# Optosense.net
KiCad netlist of a schematic drawn in Altium Designer
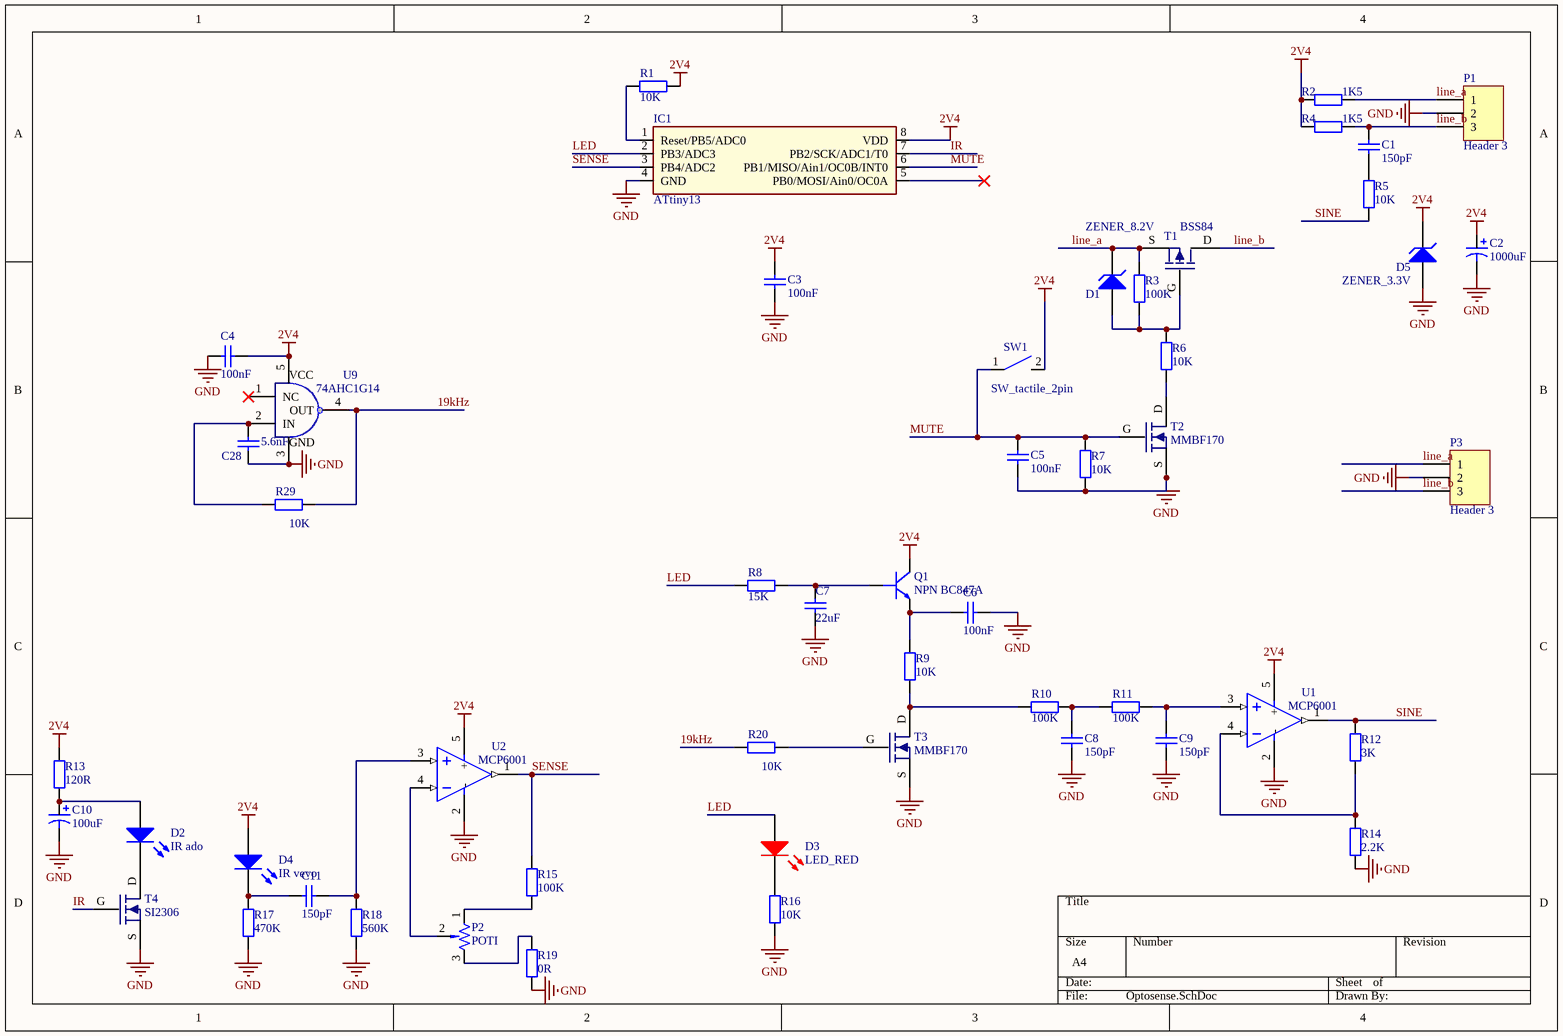
[diagram p0: Optosense.SchDoc]

(export (version "E")
  (design (tool "Eeschema 10.0.6"))
  (components
    (comp (ref "C1")
      (value "150pF")
      (footprint "FP_0603_CAP_080")
      (description "Capacitor")
      (libsource (lib "Capacitor") (part "CAP"))
    )
    (comp (ref "C2")
      (value "1000uF")
      (footprint "CAP_8x11_fekvo")
      (description "Polarized Capacitor")
      (libsource (lib "Capacitor") (part "CAP_ELECT"))
    )
    (comp (ref "C3")
      (value "100nF")
      (footprint "FP_0603_CAP_080")
      (description "Capacitor")
      (libsource (lib "Capacitor") (part "CAP"))
    )
    (comp (ref "C4")
      (value "100nF")
      (footprint "FP_0603_CAP_080")
      (description "Capacitor")
      (libsource (lib "Capacitor") (part "CAP"))
    )
    (comp (ref "C5")
      (value "100nF")
      (footprint "FP_0603_CAP_080")
      (description "Capacitor")
      (libsource (lib "Capacitor") (part "CAP"))
    )
    (comp (ref "C6")
      (value "100nF")
      (footprint "FP_0603_CAP_080")
      (description "Capacitor")
      (libsource (lib "Capacitor") (part "CAP"))
    )
    (comp (ref "C7")
      (value "22uF")
      (footprint "FP_1206_CAP_125")
      (description "Capacitor")
      (libsource (lib "Miscellaneous Devices") (part "Cap"))
    )
    (comp (ref "C8")
      (value "150pF")
      (footprint "FP_0603_CAP_080")
      (description "Capacitor")
      (libsource (lib "Capacitor") (part "CAP"))
    )
    (comp (ref "C9")
      (value "150pF")
      (footprint "FP_0603_CAP_080")
      (description "Capacitor")
      (libsource (lib "Capacitor") (part "CAP"))
    )
    (comp (ref "C10")
      (value "100uF")
      (footprint "FP_3528")
      (description "Polarized Capacitor")
      (libsource (lib "Capacitor") (part "CAP_ELECT"))
    )
    (comp (ref "C11")
      (value "150pF")
      (footprint "FP_0603_CAP_080")
      (description "Capacitor")
      (libsource (lib "Capacitor") (part "CAP"))
    )
    (comp (ref "C28")
      (value "5.6nF")
      (footprint "FP_0603_CAP_080")
      (description "Capacitor")
      (fields (field (name "PUBLISHER") "Altium Limited"))
      (libsource (lib "Miscellaneous Devices") (part "Cap"))
    )
    (comp (ref "D1")
      (value "ZENER_8.2V")
      (footprint "SOD-80")
      (description "Zener Diode")
      (libsource (lib "Diode") (part "ZENER"))
    )
    (comp (ref "D2")
      (value "IR ado")
      (footprint "LED_IR_5mm")
      (description "Typical LED")
      (libsource (lib "Led_optical") (part "LED_B"))
    )
    (comp (ref "D3")
      (value "LED_RED")
      (footprint "led_3mm_standing R")
      (description "Typical LED")
      (libsource (lib "Led_optical") (part "LED_R"))
    )
    (comp (ref "D4")
      (value "IR vevo")
      (footprint "LED_IR_5mm")
      (description "Typical LED")
      (libsource (lib "Led_optical") (part "LED_B"))
    )
    (comp (ref "D5")
      (value "ZENER_3.3V")
      (footprint "SOD-80")
      (description "Zener Diode")
      (libsource (lib "Diode") (part "ZENER"))
    )
    (comp (ref "IC1") (value "ATtiny13") (footprint "WSON_n_SOIC8") (libsource (lib "uC") (part "ATtiny13")))
    (comp (ref "P1")
      (value "Header 3")
      (footprint "HDR1X3")
      (description "Header, 3-Pin")
      (fields (field (name "PUBLISHER") "Altium Limited"))
      (libsource (lib "Miscellaneous Connectors") (part "Header 3"))
    )
    (comp (ref "P2")
      (value "POTI")
      (footprint "RES_trimmer_helipot_mini_90")
      (libsource (lib "Resistor") (part "POTI"))
    )
    (comp (ref "P3")
      (value "Header 3")
      (footprint "HDR1X3")
      (description "Header, 3-Pin")
      (fields (field (name "PUBLISHER") "Altium Limited"))
      (libsource (lib "Miscellaneous Connectors") (part "Header 3"))
    )
    (comp (ref "Q1") (value "NPN BC847A") (footprint "TR_SOT23") (libsource (lib "Transistor") (part "NPN")))
    (comp (ref "R1")
      (value "10K")
      (footprint "FP_0603_RES")
      (description "Resistor")
      (libsource (lib "") (part "RES_3"))
    )
    (comp (ref "R2")
      (value "1K5")
      (footprint "FP_0603_RES")
      (description "Resistor")
      (libsource (lib "") (part "RES_2"))
    )
    (comp (ref "R3")
      (value "100K")
      (footprint "FP_0603_RES")
      (description "Resistor")
      (libsource (lib "") (part "RES_1"))
    )
    (comp (ref "R4")
      (value "1K5")
      (footprint "FP_0603_RES")
      (description "Resistor")
      (libsource (lib "") (part "RES_2"))
    )
    (comp (ref "R5")
      (value "10K")
      (footprint "FP_0603_RES")
      (description "Resistor")
      (libsource (lib "Resistor") (part "RES"))
    )
    (comp (ref "R6")
      (value "10K")
      (footprint "FP_0603_RES")
      (description "Resistor")
      (libsource (lib "") (part "RES_1"))
    )
    (comp (ref "R7")
      (value "10K")
      (footprint "FP_0603_RES")
      (description "Resistor")
      (libsource (lib "") (part "RES_1"))
    )
    (comp (ref "R8")
      (value "15K")
      (footprint "FP_0603_RES")
      (description "Resistor")
      (libsource (lib "") (part "RES_3"))
    )
    (comp (ref "R9")
      (value "10K")
      (footprint "FP_0603_RES")
      (description "Resistor")
      (libsource (lib "") (part "RES_1"))
    )
    (comp (ref "R10")
      (value "100K")
      (footprint "FP_0603_RES")
      (description "Resistor")
      (libsource (lib "") (part "RES_3"))
    )
    (comp (ref "R11")
      (value "100K")
      (footprint "FP_0603_RES")
      (description "Resistor")
      (libsource (lib "") (part "RES_3"))
    )
    (comp (ref "R12")
      (value "3K")
      (footprint "FP_0603_RES")
      (description "Resistor")
      (libsource (lib "") (part "RES_1"))
    )
    (comp (ref "R13")
      (value "120R")
      (footprint "FP_0603_RES")
      (description "Resistor")
      (libsource (lib "Resistor") (part "RES"))
    )
    (comp (ref "R14")
      (value "2.2K")
      (footprint "FP_0603_RES")
      (description "Resistor")
      (libsource (lib "") (part "RES_1"))
    )
    (comp (ref "R15")
      (value "100K")
      (footprint "FP_0603_RES")
      (description "Resistor")
      (libsource (lib "Resistor") (part "RES"))
    )
    (comp (ref "R16")
      (value "10K")
      (footprint "FP_0603_RES")
      (description "Resistor")
      (libsource (lib "Resistor") (part "RES"))
    )
    (comp (ref "R17")
      (value "470K")
      (footprint "FP_0603_RES")
      (description "Resistor")
      (libsource (lib "Resistor") (part "RES"))
    )
    (comp (ref "R18")
      (value "560K")
      (footprint "FP_0603_RES")
      (description "Resistor")
      (libsource (lib "Resistor") (part "RES"))
    )
    (comp (ref "R19")
      (value "0R")
      (footprint "FP_0603_RES")
      (description "Resistor")
      (libsource (lib "Resistor") (part "RES"))
    )
    (comp (ref "R20")
      (value "10K")
      (footprint "FP_0603_RES")
      (description "Resistor")
      (fields (field (name "PUBLISHER") "Altium Limited"))
      (libsource (lib "Miscellaneous Devices") (part "Res3"))
    )
    (comp (ref "R29")
      (value "10K")
      (footprint "FP_0603_RES")
      (description "Resistor")
      (fields (field (name "PUBLISHER") "Altium Limited"))
      (libsource (lib "Miscellaneous Devices") (part "Res3"))
    )
    (comp (ref "SW1")
      (value "SW_tactile_2pin")
      (footprint "SW_TACT_2PIN")
      (libsource (lib "Switch") (part "SW_tactile_2pin"))
    )
    (comp (ref "T1") (value "BSS84") (footprint "FET_SOT23") (libsource (lib "FET") (part "PMOS")))
    (comp (ref "T2") (value "MMBF170") (footprint "FET_SOT23") (libsource (lib "FET") (part "NMOS")))
    (comp (ref "T3") (value "MMBF170") (footprint "FET_SOT23") (libsource (lib "FET") (part "NMOS")))
    (comp (ref "T4") (value "SI2306") (footprint "FET_SOT23") (libsource (lib "FET") (part "NMOS")))
    (comp (ref "U1")
      (value "MCP6001")
      (footprint "ANALOG_SOT23-5")
      (libsource (lib "Analog") (part "MCP6001"))
    )
    (comp (ref "U2")
      (value "MCP6001")
      (footprint "ANALOG_SOT23-5")
      (libsource (lib "Analog") (part "MCP6001"))
    )
    (comp (ref "U9")
      (value "74AHC1G14")
      (footprint "GATE_SOT23-5")
      (description "SCHMITT-TRIGGER INVERTER")
      (libsource (lib "Logic_gate") (part "74AHC1G14"))
    )
  )
  (nets
    (net (code "1") (name "/19kHz") (class "Default")
      (node (ref "R20") (pin "2") (pinfunction "2_2") (pintype "passive"))
      (node (ref "R29") (pin "1") (pinfunction "1_1") (pintype "passive"))
      (node (ref "U9") (pin "4") (pinfunction "OUT_4") (pintype "passive"))
    )
    (net (code "2") (name "/IR") (class "Default")
      (node (ref "IC1") (pin "7") (pinfunction "PB2/SCK/ADC1/T0_7") (pintype "passive"))
      (node (ref "T4") (pin "G") (pinfunction "G_G") (pintype "passive"))
    )
    (net (code "3") (name "/LED") (class "Default")
      (node (ref "D3") (pin "A") (pinfunction "A_A") (pintype "passive"))
      (node (ref "IC1") (pin "2") (pinfunction "PB3/ADC3_2") (pintype "passive"))
      (node (ref "R8") (pin "2") (pinfunction "2_2") (pintype "passive"))
    )
    (net (code "4") (name "/MUTE") (class "Default")
      (node (ref "C5") (pin "2") (pinfunction "2_2") (pintype "passive"))
      (node (ref "IC1") (pin "6") (pinfunction "PB1/MISO/Ain1/OC0B/INT0_6") (pintype "passive"))
      (node (ref "R7") (pin "1") (pinfunction "1_1") (pintype "passive"))
      (node (ref "SW1") (pin "1") (pinfunction "1_1") (pintype "passive"))
      (node (ref "T2") (pin "G") (pinfunction "G_G") (pintype "passive"))
    )
    (net (code "5") (name "/SENSE") (class "Default")
      (node (ref "IC1") (pin "3") (pinfunction "PB4/ADC2_3") (pintype "passive"))
      (node (ref "R15") (pin "2") (pinfunction "2_2") (pintype "passive"))
      (node (ref "U2") (pin "1") (pinfunction "OUT1_1") (pintype "output"))
    )
    (net (code "6") (name "/SINE") (class "Default")
      (node (ref "R12") (pin "1") (pinfunction "1_1") (pintype "passive"))
      (node (ref "R5") (pin "1") (pinfunction "1_1") (pintype "passive"))
      (node (ref "U1") (pin "1") (pinfunction "OUT1_1") (pintype "output"))
    )
    (net (code "7") (name "/line_a") (class "Default")
      (node (ref "D1") (pin "K") (pinfunction "K_K") (pintype "passive"))
      (node (ref "P1") (pin "1") (pinfunction "1_1") (pintype "passive"))
      (node (ref "P3") (pin "1") (pinfunction "1_1") (pintype "passive"))
      (node (ref "R2") (pin "2") (pinfunction "2_2") (pintype "passive"))
      (node (ref "R3") (pin "1") (pinfunction "1_1") (pintype "passive"))
      (node (ref "T1") (pin "S") (pinfunction "S_S") (pintype "passive"))
    )
    (net (code "8") (name "/line_b") (class "Default")
      (node (ref "C1") (pin "2") (pinfunction "2_2") (pintype "passive"))
      (node (ref "P1") (pin "3") (pinfunction "3_3") (pintype "passive"))
      (node (ref "P3") (pin "3") (pinfunction "3_3") (pintype "passive"))
      (node (ref "R4") (pin "2") (pinfunction "2_2") (pintype "passive"))
      (node (ref "T1") (pin "D") (pinfunction "D_D") (pintype "passive"))
    )
    (net (code "9") (name "2V4") (class "Default")
      (node (ref "C2") (pin "P") (pintype "passive"))
      (node (ref "C3") (pin "2") (pinfunction "2_2") (pintype "passive"))
      (node (ref "C4") (pin "1") (pinfunction "1_1") (pintype "passive"))
      (node (ref "D4") (pin "A") (pinfunction "A_A") (pintype "passive"))
      (node (ref "D5") (pin "K") (pinfunction "K_K") (pintype "passive"))
      (node (ref "IC1") (pin "8") (pinfunction "VDD_8") (pintype "passive"))
      (node (ref "Q1") (pin "C") (pinfunction "C_C") (pintype "passive"))
      (node (ref "R1") (pin "1") (pinfunction "1_1") (pintype "passive"))
      (node (ref "R13") (pin "2") (pinfunction "2_2") (pintype "passive"))
      (node (ref "R2") (pin "1") (pinfunction "1_1") (pintype "passive"))
      (node (ref "R4") (pin "1") (pinfunction "1_1") (pintype "passive"))
      (node (ref "SW1") (pin "2") (pinfunction "2_2") (pintype "passive"))
      (node (ref "U1") (pin "5") (pinfunction "+_5") (pintype "power_in"))
      (node (ref "U2") (pin "5") (pinfunction "+_5") (pintype "power_in"))
      (node (ref "U9") (pin "5") (pinfunction "VCC_5") (pintype "passive"))
    )
    (net (code "10") (name "GND") (class "Default")
      (node (ref "C10") (pin "N") (pintype "passive"))
      (node (ref "C2") (pin "N") (pintype "passive"))
      (node (ref "C28") (pin "1") (pinfunction "1_1") (pintype "passive"))
      (node (ref "C3") (pin "1") (pinfunction "1_1") (pintype "passive"))
      (node (ref "C4") (pin "2") (pinfunction "2_2") (pintype "passive"))
      (node (ref "C5") (pin "1") (pinfunction "1_1") (pintype "passive"))
      (node (ref "C6") (pin "1") (pinfunction "1_1") (pintype "passive"))
      (node (ref "C7") (pin "1") (pinfunction "1_1") (pintype "passive"))
      (node (ref "C8") (pin "1") (pinfunction "1_1") (pintype "passive"))
      (node (ref "C9") (pin "1") (pinfunction "1_1") (pintype "passive"))
      (node (ref "D5") (pin "A") (pinfunction "A_A") (pintype "passive"))
      (node (ref "IC1") (pin "4") (pinfunction "GND_4") (pintype "passive"))
      (node (ref "P1") (pin "2") (pinfunction "2_2") (pintype "passive"))
      (node (ref "P3") (pin "2") (pinfunction "2_2") (pintype "passive"))
      (node (ref "R14") (pin "2") (pinfunction "2_2") (pintype "passive"))
      (node (ref "R16") (pin "1") (pinfunction "1_1") (pintype "passive"))
      (node (ref "R17") (pin "1") (pinfunction "1_1") (pintype "passive"))
      (node (ref "R18") (pin "1") (pinfunction "1_1") (pintype "passive"))
      (node (ref "R19") (pin "1") (pinfunction "1_1") (pintype "passive"))
      (node (ref "R7") (pin "2") (pinfunction "2_2") (pintype "passive"))
      (node (ref "T2") (pin "S") (pinfunction "S_S") (pintype "passive"))
      (node (ref "T3") (pin "S") (pinfunction "S_S") (pintype "passive"))
      (node (ref "T4") (pin "S") (pinfunction "S_S") (pintype "passive"))
      (node (ref "U1") (pin "2") (pinfunction "-_2") (pintype "power_in"))
      (node (ref "U2") (pin "2") (pinfunction "-_2") (pintype "power_in"))
      (node (ref "U9") (pin "3") (pinfunction "GND_3") (pintype "passive"))
    )
    (net (code "11") (name "Net-(C1-Pad1)") (class "Default")
      (node (ref "C1") (pin "1") (pinfunction "1_1") (pintype "passive"))
      (node (ref "R5") (pin "2") (pinfunction "2_2") (pintype "passive"))
    )
    (net (code "12") (name "Net-(C6-Pad2)") (class "Default")
      (node (ref "C6") (pin "2") (pinfunction "2_2") (pintype "passive"))
      (node (ref "Q1") (pin "E") (pinfunction "E_E") (pintype "passive"))
      (node (ref "R9") (pin "1") (pinfunction "1_1") (pintype "passive"))
    )
    (net (code "13") (name "Net-(C7-Pad2)") (class "Default")
      (node (ref "C7") (pin "2") (pinfunction "2_2") (pintype "passive"))
      (node (ref "Q1") (pin "B") (pinfunction "B_B") (pintype "passive"))
      (node (ref "R8") (pin "1") (pinfunction "1_1") (pintype "passive"))
    )
    (net (code "14") (name "Net-(C8-Pad2)") (class "Default")
      (node (ref "C8") (pin "2") (pinfunction "2_2") (pintype "passive"))
      (node (ref "R10") (pin "1") (pinfunction "1_1") (pintype "passive"))
      (node (ref "R11") (pin "2") (pinfunction "2_2") (pintype "passive"))
    )
    (net (code "15") (name "Net-(C10-PadP)") (class "Default")
      (node (ref "C10") (pin "P") (pintype "passive"))
      (node (ref "D2") (pin "A") (pinfunction "A_A") (pintype "passive"))
      (node (ref "R13") (pin "1") (pinfunction "1_1") (pintype "passive"))
    )
    (net (code "16") (name "Net-(C11-Pad1)") (class "Default")
      (node (ref "C11") (pin "1") (pinfunction "1_1") (pintype "passive"))
      (node (ref "D4") (pin "K") (pinfunction "K_K") (pintype "passive"))
      (node (ref "R17") (pin "2") (pinfunction "2_2") (pintype "passive"))
    )
    (net (code "17") (name "Net-(D1-PadA)") (class "Default")
      (node (ref "D1") (pin "A") (pinfunction "A_A") (pintype "passive"))
      (node (ref "R3") (pin "2") (pinfunction "2_2") (pintype "passive"))
      (node (ref "R6") (pin "1") (pinfunction "1_1") (pintype "passive"))
      (node (ref "T1") (pin "G") (pinfunction "G_G") (pintype "passive"))
    )
    (net (code "18") (name "Net-(D2-PadK)") (class "Default")
      (node (ref "D2") (pin "K") (pinfunction "K_K") (pintype "passive"))
      (node (ref "T4") (pin "D") (pinfunction "D_D") (pintype "passive"))
    )
    (net (code "19") (name "Net-(D3-PadK)") (class "Default")
      (node (ref "D3") (pin "K") (pinfunction "K_K") (pintype "passive"))
      (node (ref "R16") (pin "2") (pinfunction "2_2") (pintype "passive"))
    )
    (net (code "20") (name "Net-(IC1-Reset{slash}PB5{slash}ADC0)") (class "Default")
      (node (ref "IC1") (pin "1") (pinfunction "Reset/PB5/ADC0_1") (pintype "passive"))
      (node (ref "R1") (pin "2") (pinfunction "2_2") (pintype "passive"))
    )
    (net (code "21") (name "Net-(P2-2)") (class "Default")
      (node (ref "P2") (pin "3") (pinfunction "2_3") (pintype "passive"))
      (node (ref "R19") (pin "2") (pinfunction "2_2") (pintype "passive"))
    )
    (net (code "22") (name "Net-(P2-Pad1)") (class "Default")
      (node (ref "P2") (pin "1") (pinfunction "1_1") (pintype "passive"))
      (node (ref "R15") (pin "1") (pinfunction "1_1") (pintype "passive"))
    )
    (net (code "23") (name "Net-(P2-t)") (class "Default")
      (node (ref "P2") (pin "2") (pinfunction "t_2") (pintype "passive"))
      (node (ref "U2") (pin "4") (pinfunction "IN1-_4") (pintype "input"))
    )
    (net (code "24") (name "Net-(R6-Pad2)") (class "Default")
      (node (ref "R6") (pin "2") (pinfunction "2_2") (pintype "passive"))
      (node (ref "T2") (pin "D") (pinfunction "D_D") (pintype "passive"))
    )
    (net (code "25") (name "Net-(R10-Pad2)") (class "Default")
      (node (ref "R10") (pin "2") (pinfunction "2_2") (pintype "passive"))
      (node (ref "R9") (pin "2") (pinfunction "2_2") (pintype "passive"))
      (node (ref "T3") (pin "D") (pinfunction "D_D") (pintype "passive"))
    )
    (net (code "26") (name "Net-(R20-Pad1)") (class "Default")
      (node (ref "R20") (pin "1") (pinfunction "1_1") (pintype "passive"))
      (node (ref "T3") (pin "G") (pinfunction "G_G") (pintype "passive"))
    )
    (net (code "27") (name "Net-(U1-IN1+)") (class "Default")
      (node (ref "C9") (pin "2") (pinfunction "2_2") (pintype "passive"))
      (node (ref "R11") (pin "1") (pinfunction "1_1") (pintype "passive"))
      (node (ref "U1") (pin "3") (pinfunction "IN1+_3") (pintype "input"))
    )
    (net (code "28") (name "Net-(U1-IN1-)") (class "Default")
      (node (ref "R12") (pin "2") (pinfunction "2_2") (pintype "passive"))
      (node (ref "R14") (pin "1") (pinfunction "1_1") (pintype "passive"))
      (node (ref "U1") (pin "4") (pinfunction "IN1-_4") (pintype "input"))
    )
    (net (code "29") (name "Net-(U2-IN1+)") (class "Default")
      (node (ref "C11") (pin "2") (pinfunction "2_2") (pintype "passive"))
      (node (ref "R18") (pin "2") (pinfunction "2_2") (pintype "passive"))
      (node (ref "U2") (pin "3") (pinfunction "IN1+_3") (pintype "input"))
    )
    (net (code "30") (name "Net-(U9-IN)") (class "Default")
      (node (ref "C28") (pin "2") (pinfunction "2_2") (pintype "passive"))
      (node (ref "R29") (pin "2") (pinfunction "2_2") (pintype "passive"))
      (node (ref "U9") (pin "2") (pinfunction "IN_2") (pintype "passive"))
    )
    (net (code "31") (name "unconnected-(IC1-PB0{slash}MOSI{slash}Ain0{slash}OC0A-Pad5)") (class "Default")
      (node (ref "IC1") (pin "5") (pinfunction "PB0/MOSI/Ain0/OC0A_5") (pintype "passive+no_connect"))
    )
    (net (code "32") (name "unconnected-(U9-NC-Pad1)") (class "Default")
      (node (ref "U9") (pin "1") (pinfunction "NC_1") (pintype "passive+no_connect"))
    )
  )
)
